# Sheet_Arduino_Mega_2560.net
KiCad netlist of a schematic drawn in Altium Designer
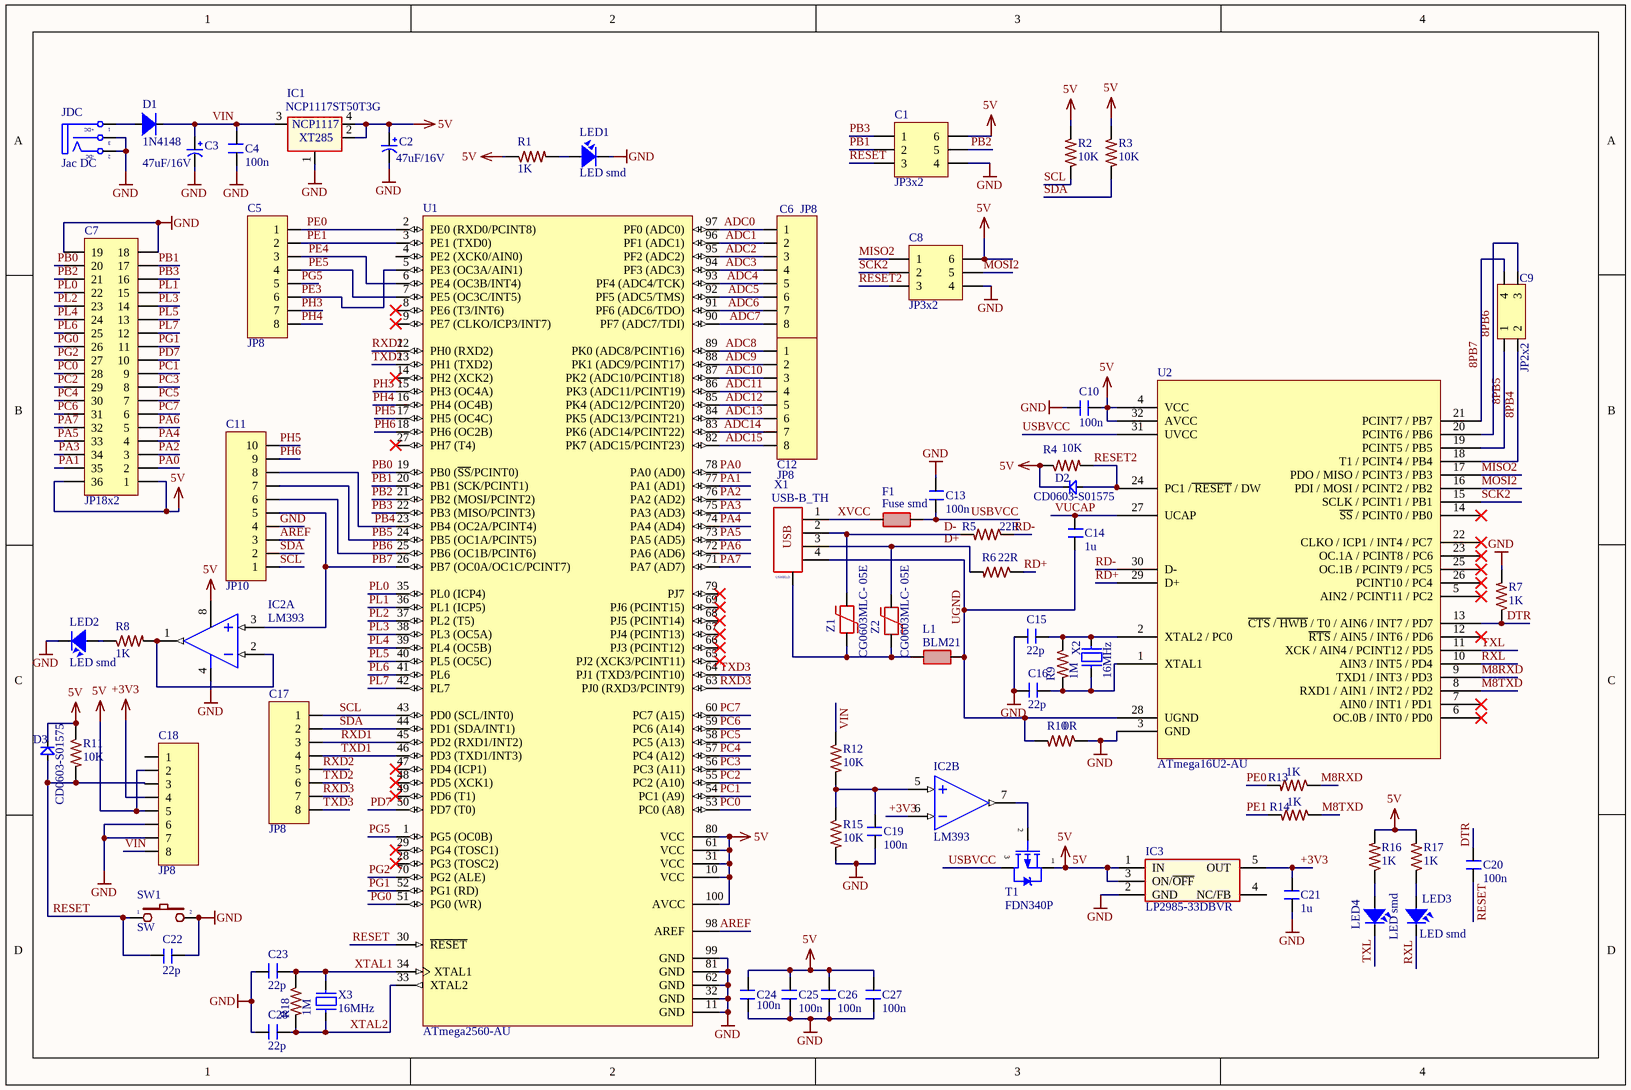
[diagram p0: Sheet_Arduino_Mega_2560.SchDoc]

(export (version "E")
  (design (tool "Eeschema 10.0.6"))
  (components
    (comp (ref "C1")
      (value "JP3x2")
      (footprint "JP3-D2T")
      (description "WR-PHD 2.54 mm Dual Socket Header")
      (fields
        (field (name "MANUFACTURER") "Würth Elektronik eiSos GmbH")
        (field (name "PARTNO") "61300621821")
        (field (name "CREATED BY") "Karrer Zheng")
      )
      (libsource (lib "APESLAB") (part "JP3x2"))
    )
    (comp (ref "C2")
      (value "47uF/16V")
      (footprint "CAP-ALU-SMD-F")
      (description "Cap 47uF/16V")
      (libsource (lib "APESLAB") (part "Cap 47uF/16V"))
    )
    (comp (ref "C3")
      (value "47uF/16V")
      (footprint "CAP-ALU-SMD-F")
      (description "Cap 47uF/16V")
      (libsource (lib "APESLAB") (part "Cap 47uF/16V"))
    )
    (comp (ref "C4")
      (value "100n")
      (footprint "cap 0603")
      (description "100nF±5%/5V")
      (libsource (lib "APESLAB") (part "Cap"))
    )
    (comp (ref "C5")
      (value "JP8")
      (footprint "JP8-C1T")
      (description "WR-PHD 2.54 mm Angled Socket Header")
      (fields
        (field (name "MANUFACTURER") "Würth Elektronik eiSos GmbH")
        (field (name "PARTNO") "613008143121")
        (field (name "CREATED BY") "Karrer Zheng")
      )
      (libsource (lib "") (part "JP8_1"))
    )
    (comp (ref "C6")
      (value "JP8")
      (footprint "JP8-C1T")
      (description "WR-PHD 2.54 mm Angled Socket Header")
      (fields
        (field (name "MANUFACTURER") "Würth Elektronik eiSos GmbH")
        (field (name "PARTNO") "613008143121")
        (field (name "CREATED BY") "Karrer Zheng")
      )
      (libsource (lib "APESLAB") (part "JP8"))
    )
    (comp (ref "C7")
      (value "JP18x2")
      (footprint "JP18-C2T")
      (description "WR-PHD 2.54 mm Dual Socket Header")
      (fields
        (field (name "MANUFACTURER") "Würth Elektronik eiSos GmbH")
        (field (name "PARTNO") "61303621821")
        (field (name "CREATED BY") "Karrer Zheng")
      )
      (libsource (lib "APESLAB") (part "JP18x2"))
    )
    (comp (ref "C8")
      (value "JP3x2")
      (footprint "JP3-D2T")
      (description "WR-PHD 2.54 mm Dual Socket Header")
      (fields
        (field (name "MANUFACTURER") "Würth Elektronik eiSos GmbH")
        (field (name "PARTNO") "61300621821")
        (field (name "CREATED BY") "Karrer Zheng")
      )
      (libsource (lib "APESLAB") (part "JP3x2"))
    )
    (comp (ref "C9")
      (value "JP2x2")
      (footprint "JP2-D2T")
      (description "WR-PHD 2.54 mm Dual Socket Header")
      (fields
        (field (name "MANUFACTURER") "Würth Elektronik eiSos GmbH")
        (field (name "PARTNO") "61300421821")
        (field (name "CREATED BY") "Karrer Zheng")
      )
      (libsource (lib "APESLAB") (part "JP2x2"))
    )
    (comp (ref "C10")
      (value "100n")
      (footprint "cap 0603")
      (description "100nF±5%/5V")
      (libsource (lib "APESLAB") (part "Cap"))
    )
    (comp (ref "C11")
      (value "JP10")
      (footprint "JP10-C1T")
      (description "WR-PHD 2.54 mm Angled Socket Header")
      (fields
        (field (name "MANUFACTURER") "Würth Elektronik eiSos GmbH")
        (field (name "PARTNO") "613010143121")
        (field (name "CREATED BY") "Karrer Zheng")
      )
      (libsource (lib "APESLAB") (part "JP10"))
    )
    (comp (ref "C12")
      (value "JP8")
      (footprint "JP8-C1T")
      (description "WR-PHD 2.54 mm Angled Socket Header")
      (fields
        (field (name "MANUFACTURER") "Würth Elektronik eiSos GmbH")
        (field (name "PARTNO") "613008143121")
        (field (name "CREATED BY") "Karrer Zheng")
      )
      (libsource (lib "APESLAB") (part "JP8"))
    )
    (comp (ref "C13")
      (value "100n")
      (footprint "cap 0603")
      (description "100nF±5%/5V")
      (libsource (lib "APESLAB") (part "Cap"))
    )
    (comp (ref "C14")
      (value "1u")
      (footprint "cap 0603")
      (description "0.47uF/1.6kV")
      (libsource (lib "APESLAB") (part "Cap"))
    )
    (comp (ref "C15")
      (value "22p")
      (footprint "cap 0603")
      (description "0.47uF/1.6kV")
      (libsource (lib "APESLAB") (part "Cap"))
    )
    (comp (ref "C16")
      (value "22p")
      (footprint "cap 0603")
      (description "0.47uF/1.6kV")
      (libsource (lib "APESLAB") (part "Cap"))
    )
    (comp (ref "C17")
      (value "JP8")
      (footprint "JP8-C1T")
      (description "WR-PHD 2.54 mm Angled Socket Header")
      (fields
        (field (name "MANUFACTURER") "Würth Elektronik eiSos GmbH")
        (field (name "PARTNO") "613008143121")
        (field (name "CREATED BY") "Karrer Zheng")
      )
      (libsource (lib "") (part "JP8_1"))
    )
    (comp (ref "C18")
      (value "JP8")
      (footprint "JP8-C1T")
      (description "WR-PHD 2.54 mm Angled Socket Header")
      (fields
        (field (name "MANUFACTURER") "Würth Elektronik eiSos GmbH")
        (field (name "PARTNO") "613008143121")
        (field (name "CREATED BY") "Karrer Zheng")
      )
      (libsource (lib "APESLAB") (part "JP8"))
    )
    (comp (ref "C19")
      (value "100n")
      (footprint "cap 0603")
      (description "100nF±5%/5V")
      (libsource (lib "APESLAB") (part "Cap"))
    )
    (comp (ref "C20")
      (value "100n")
      (footprint "cap 0603")
      (description "100nF±5%/5V")
      (libsource (lib "APESLAB") (part "Cap"))
    )
    (comp (ref "C21")
      (value "1u")
      (footprint "cap 0603")
      (description "0.47uF/1.6kV")
      (libsource (lib "APESLAB") (part "Cap"))
    )
    (comp (ref "C22")
      (value "22p")
      (footprint "cap 0603")
      (description "0.47uF/1.6kV")
      (libsource (lib "APESLAB") (part "Cap"))
    )
    (comp (ref "C23")
      (value "22p")
      (footprint "cap 0603")
      (description "0.47uF/1.6kV")
      (libsource (lib "APESLAB") (part "Cap"))
    )
    (comp (ref "C24")
      (value "100n")
      (footprint "cap 0603")
      (description "100nF±5%/5V")
      (libsource (lib "APESLAB") (part "Cap"))
    )
    (comp (ref "C25")
      (value "100n")
      (footprint "cap 0603")
      (description "100nF±5%/5V")
      (libsource (lib "APESLAB") (part "Cap"))
    )
    (comp (ref "C26")
      (value "100n")
      (footprint "cap 0603")
      (description "100nF±5%/5V")
      (libsource (lib "APESLAB") (part "Cap"))
    )
    (comp (ref "C27")
      (value "100n")
      (footprint "cap 0603")
      (description "100nF±5%/5V")
      (libsource (lib "APESLAB") (part "Cap"))
    )
    (comp (ref "C28")
      (value "22p")
      (footprint "cap 0603")
      (description "0.47uF/1.6kV")
      (libsource (lib "APESLAB") (part "Cap"))
    )
    (comp (ref "D1")
      (value "1N4148")
      (footprint "SOD80_lib")
      (libsource (lib "APESLAB") (part "Diode 1N4148"))
    )
    (comp (ref "D2")
      (value "CD0603-S01575")
      (footprint "CD0603-S01575")
      (description "diode CD0603-S01575")
      (libsource (lib "APESLAB") (part "CD0603-S01575"))
    )
    (comp (ref "D3")
      (value "CD0603-S01575")
      (footprint "CD0603-S01575")
      (description "diode CD0603-S01575")
      (libsource (lib "APESLAB") (part "CD0603-S01575"))
    )
    (comp (ref "F1") (value "Fuse smd") (footprint "Fuse_smd") (libsource (lib "APESLAB") (part "Fuse_smd")))
    (comp (ref "IC1")
      (value "NCP1117ST50T3G")
      (footprint "SOT223-4M_apes")
      (description "NCP1117")
      (libsource (lib "APESLAB") (part "NCP1117ST50T3G"))
    )
    (comp (ref "IC2")
      (value "LM393")
      (footprint "LM393")
      (description "Low-Power Dual Operational Amplifier")
      (libsource (lib "APESLAB") (part "LM393"))
    )
    (comp (ref "IC3")
      (value "LP2985-33DBVR")
      (footprint "SOT23-5")
      (libsource (lib "APESLAB") (part "LP2985"))
    )
    (comp (ref "JDC")
      (value "Jac DC")
      (footprint "DC0")
      (description "Jac DC input")
      (libsource (lib "APESLAB") (part "DCIN"))
    )
    (comp (ref "L1")
      (value "BLM21")
      (footprint "BLM21")
      (description "BLM21 EMI")
      (libsource (lib "APESLAB") (part "BLM21"))
    )
    (comp (ref "LED1")
      (value "LED smd")
      (footprint "LED-0805-Yellow")
      (libsource (lib "APESLAB") (part "LED smd"))
    )
    (comp (ref "LED2")
      (value "LED smd")
      (footprint "LED-0805-Red")
      (libsource (lib "APESLAB") (part "LED smd"))
    )
    (comp (ref "LED3")
      (value "LED smd")
      (footprint "LED-0805-Yellow")
      (libsource (lib "APESLAB") (part "LED smd"))
    )
    (comp (ref "LED4")
      (value "LED smd")
      (footprint "LED-0805-Yellow")
      (libsource (lib "APESLAB") (part "LED smd"))
    )
    (comp (ref "R1")
      (value "1K")
      (footprint "RES-SMD-0603")
      (description "res smd")
      (libsource (lib "APESLAB") (part "RES SMD"))
    )
    (comp (ref "R2")
      (value "10K")
      (footprint "RES-SMD-0603")
      (description "10K±1%/0.25W")
      (libsource (lib "APESLAB") (part "RES SMD"))
    )
    (comp (ref "R3")
      (value "10K")
      (footprint "RES-SMD-0603")
      (description "10K±1%/0.25W")
      (libsource (lib "APESLAB") (part "RES SMD"))
    )
    (comp (ref "R4")
      (value "10K")
      (footprint "RES-SMD-0603")
      (description "10K±1%/0.25W")
      (libsource (lib "APESLAB") (part "RES SMD"))
    )
    (comp (ref "R5")
      (value "22R")
      (footprint "RES-SMD-0603")
      (description "res smd")
      (libsource (lib "APESLAB") (part "RES SMD"))
    )
    (comp (ref "R6")
      (value "22R")
      (footprint "RES-SMD-0603")
      (description "res smd")
      (libsource (lib "APESLAB") (part "RES SMD"))
    )
    (comp (ref "R7")
      (value "1K")
      (footprint "RES-SMD-0603")
      (description "res smd")
      (libsource (lib "APESLAB") (part "RES SMD"))
    )
    (comp (ref "R8")
      (value "1K")
      (footprint "RES-SMD-0603")
      (description "res smd")
      (libsource (lib "APESLAB") (part "RES SMD"))
    )
    (comp (ref "R9")
      (value "1M")
      (footprint "RES-SMD-0603")
      (description "res smd")
      (libsource (lib "APESLAB") (part "RES SMD"))
    )
    (comp (ref "R10")
      (value "0R")
      (footprint "RES-SMD-0603")
      (description "res smd")
      (libsource (lib "APESLAB") (part "RES SMD"))
    )
    (comp (ref "R11")
      (value "10K")
      (footprint "RES-SMD-0603")
      (description "10K±1%/0.25W")
      (libsource (lib "APESLAB") (part "RES SMD"))
    )
    (comp (ref "R12")
      (value "10K")
      (footprint "RES-SMD-0603")
      (description "10K±1%/0.25W")
      (libsource (lib "APESLAB") (part "RES SMD"))
    )
    (comp (ref "R13")
      (value "1K")
      (footprint "RES-SMD-0603")
      (description "res smd")
      (libsource (lib "APESLAB") (part "RES SMD"))
    )
    (comp (ref "R14")
      (value "1K")
      (footprint "RES-SMD-0603")
      (description "res smd")
      (libsource (lib "APESLAB") (part "RES SMD"))
    )
    (comp (ref "R15")
      (value "10K")
      (footprint "RES-SMD-0603")
      (description "10K±1%/0.25W")
      (libsource (lib "APESLAB") (part "RES SMD"))
    )
    (comp (ref "R16")
      (value "1K")
      (footprint "RES-SMD-0603")
      (description "res smd")
      (libsource (lib "APESLAB") (part "RES SMD"))
    )
    (comp (ref "R17")
      (value "1K")
      (footprint "RES-SMD-0603")
      (description "res smd")
      (libsource (lib "APESLAB") (part "RES SMD"))
    )
    (comp (ref "R18")
      (value "1M")
      (footprint "RES-SMD-0603")
      (description "res smd")
      (libsource (lib "APESLAB") (part "RES SMD"))
    )
    (comp (ref "SW1")
      (value "SW")
      (footprint "SW-SMD_apes")
      (description "Switch button 2 pin")
      (libsource (lib "APESLAB") (part "SW2"))
    )
    (comp (ref "T1") (value "FDN340P") (footprint "SOT23-231") (libsource (lib "APESLAB") (part "FDN340D")))
    (comp (ref "U1")
      (value "ATmega2560-AU")
      (footprint "TQFP100L")
      (libsource (lib "APESLAB") (part "ATmega2560-AU"))
    )
    (comp (ref "U2")
      (value "ATmega16U2-AU")
      (footprint "TQFP32")
      (description "IC MCU 8BIT 16KB FLASH 32TQFP")
      (fields
        (field (name "MANUFACTURER") "Atmel")
        (field (name "MANUFACTURER PART NUMBER") "ATMEGA16U2-AU")
        (field (name ".CREATOR") "MM")
        (field (name ".CHECKED PCB") "RF")
        (field (name ".CHECKED SCH") "RF")
      )
      (libsource (lib "APESLAB") (part "ATmega16U2-AU"))
    )
    (comp (ref "X1") (value "USB-B_TH") (footprint "USB-C2") (libsource (lib "APESLAB") (part "USB-B")))
    (comp (ref "X2")
      (value "16MHz")
      (footprint "XT2-32.768KHz-2_V")
      (description "Crystal, 32.768 KHz, -40 to 85 degC, 3.2 x 1.5 x 0.9 mm SMD")
      (libsource (lib "APESLAB") (part "XT2_1"))
    )
    (comp (ref "X3")
      (value "16MHz")
      (footprint "XT2-32.768KHz-2_V")
      (description "Crystal, 32.768 KHz, -40 to 85 degC, 3.2 x 1.5 x 0.9 mm SMD")
      (libsource (lib "APESLAB") (part "XT2_1"))
    )
    (comp (ref "Z1")
      (value "CG0603MLC- 05E")
      (footprint "CG0603MLC- 05E")
      (description "EMI CG0603MLC- 05E")
      (libsource (lib "APESLAB") (part "CG0603MLC- 05E"))
    )
    (comp (ref "Z2")
      (value "CG0603MLC- 05E")
      (footprint "CG0603MLC- 05E")
      (description "EMI CG0603MLC- 05E")
      (libsource (lib "APESLAB") (part "CG0603MLC- 05E"))
    )
  )
  (nets
    (net (code "1") (name "+3V3") (class "Default")
      (node (ref "C18") (pin "4") (pinfunction "4_4") (pintype "passive"))
      (node (ref "C21") (pin "2") (pinfunction "2_2") (pintype "passive"))
      (node (ref "IC2") (pin "6") (pinfunction "IN-_6") (pintype "input"))
      (node (ref "IC3") (pin "5") (pinfunction "OUT_5") (pintype "passive"))
    )
    (net (code "2") (name "/8PB4") (class "Default")
      (node (ref "C9") (pin "2") (pinfunction "2_2") (pintype "passive"))
      (node (ref "U2") (pin "18") (pinfunction "T1_/_PCINT4_/_PB4_18") (pintype "passive"))
    )
    (net (code "3") (name "/8PB5") (class "Default")
      (node (ref "C9") (pin "1") (pinfunction "1_1") (pintype "passive"))
      (node (ref "U2") (pin "19") (pinfunction "PCINT5_/_PB5_19") (pintype "passive"))
    )
    (net (code "4") (name "/8PB6") (class "Default")
      (node (ref "C9") (pin "3") (pinfunction "3_3") (pintype "passive"))
      (node (ref "U2") (pin "20") (pinfunction "PCINT6_/_PB6_20") (pintype "passive"))
    )
    (net (code "5") (name "/8PB7") (class "Default")
      (node (ref "C9") (pin "4") (pinfunction "4_4") (pintype "passive"))
      (node (ref "U2") (pin "21") (pinfunction "PCINT7_/_PB7_21") (pintype "passive"))
    )
    (net (code "6") (name "/ADC0") (class "Default")
      (node (ref "C6") (pin "1") (pinfunction "1_1") (pintype "passive"))
      (node (ref "U1") (pin "97") (pinfunction "PF0_(ADC0)_97") (pintype "bidirectional"))
    )
    (net (code "7") (name "/ADC1") (class "Default")
      (node (ref "C6") (pin "2") (pinfunction "2_2") (pintype "passive"))
      (node (ref "U1") (pin "96") (pinfunction "PF1_(ADC1)_96") (pintype "bidirectional"))
    )
    (net (code "8") (name "/ADC2") (class "Default")
      (node (ref "C6") (pin "3") (pinfunction "3_3") (pintype "passive"))
      (node (ref "U1") (pin "95") (pinfunction "PF2_(ADC2)_95") (pintype "bidirectional"))
    )
    (net (code "9") (name "/ADC3") (class "Default")
      (node (ref "C6") (pin "4") (pinfunction "4_4") (pintype "passive"))
      (node (ref "U1") (pin "94") (pinfunction "PF3_(ADC3)_94") (pintype "bidirectional"))
    )
    (net (code "10") (name "/ADC4") (class "Default")
      (node (ref "C6") (pin "5") (pinfunction "5_5") (pintype "passive"))
      (node (ref "U1") (pin "93") (pinfunction "PF4_(ADC4/TCK)_93") (pintype "bidirectional"))
    )
    (net (code "11") (name "/ADC5") (class "Default")
      (node (ref "C6") (pin "6") (pinfunction "6_6") (pintype "passive"))
      (node (ref "U1") (pin "92") (pinfunction "PF5_(ADC5/TMS)_92") (pintype "bidirectional"))
    )
    (net (code "12") (name "/ADC6") (class "Default")
      (node (ref "C6") (pin "7") (pinfunction "7_7") (pintype "passive"))
      (node (ref "U1") (pin "91") (pinfunction "PF6_(ADC6/TDO)_91") (pintype "bidirectional"))
    )
    (net (code "13") (name "/ADC7") (class "Default")
      (node (ref "C6") (pin "8") (pinfunction "8_8") (pintype "passive"))
      (node (ref "U1") (pin "90") (pinfunction "PF7_(ADC7/TDI)_90") (pintype "bidirectional"))
    )
    (net (code "14") (name "/ADC8") (class "Default")
      (node (ref "C12") (pin "1") (pinfunction "1_1") (pintype "passive"))
      (node (ref "U1") (pin "89") (pinfunction "PK0_(ADC8/PCINT16)_89") (pintype "bidirectional"))
    )
    (net (code "15") (name "/ADC9") (class "Default")
      (node (ref "C12") (pin "2") (pinfunction "2_2") (pintype "passive"))
      (node (ref "U1") (pin "88") (pinfunction "PK1_(ADC9/PCINT17)_88") (pintype "bidirectional"))
    )
    (net (code "16") (name "/ADC10") (class "Default")
      (node (ref "C12") (pin "3") (pinfunction "3_3") (pintype "passive"))
      (node (ref "U1") (pin "87") (pinfunction "PK2_(ADC10/PCINT18)_87") (pintype "bidirectional"))
    )
    (net (code "17") (name "/ADC11") (class "Default")
      (node (ref "C12") (pin "4") (pinfunction "4_4") (pintype "passive"))
      (node (ref "U1") (pin "86") (pinfunction "PK3_(ADC11/PCINT19)_86") (pintype "bidirectional"))
    )
    (net (code "18") (name "/ADC12") (class "Default")
      (node (ref "C12") (pin "5") (pinfunction "5_5") (pintype "passive"))
      (node (ref "U1") (pin "85") (pinfunction "PK4_(ADC12/PCINT20)_85") (pintype "bidirectional"))
    )
    (net (code "19") (name "/ADC13") (class "Default")
      (node (ref "C12") (pin "6") (pinfunction "6_6") (pintype "passive"))
      (node (ref "U1") (pin "84") (pinfunction "PK5_(ADC13/PCINT21)_84") (pintype "bidirectional"))
    )
    (net (code "20") (name "/ADC14") (class "Default")
      (node (ref "C12") (pin "7") (pinfunction "7_7") (pintype "passive"))
      (node (ref "U1") (pin "83") (pinfunction "PK6_(ADC14/PCINT22)_83") (pintype "bidirectional"))
    )
    (net (code "21") (name "/ADC15") (class "Default")
      (node (ref "C12") (pin "8") (pinfunction "8_8") (pintype "passive"))
      (node (ref "U1") (pin "82") (pinfunction "PK7_(ADC15/PCINT23)_82") (pintype "bidirectional"))
    )
    (net (code "22") (name "/AREF") (class "Default")
      (node (ref "C11") (pin "3") (pinfunction "3_3") (pintype "passive"))
      (node (ref "U1") (pin "98") (pinfunction "AREF_98") (pintype "power_in"))
    )
    (net (code "23") (name "/D+") (class "Default")
      (node (ref "R6") (pin "2") (pinfunction "2_2") (pintype "passive"))
      (node (ref "X1") (pin "3") (pinfunction "3_3") (pintype "passive"))
      (node (ref "Z2") (pin "2") (pinfunction "2_2") (pintype "passive"))
    )
    (net (code "24") (name "/D-") (class "Default")
      (node (ref "R5") (pin "2") (pinfunction "2_2") (pintype "passive"))
      (node (ref "X1") (pin "2") (pinfunction "2_2") (pintype "passive"))
      (node (ref "Z1") (pin "2") (pinfunction "2_2") (pintype "passive"))
    )
    (net (code "25") (name "/DTR") (class "Default")
      (node (ref "C20") (pin "1") (pinfunction "1_1") (pintype "passive"))
      (node (ref "R7") (pin "1") (pinfunction "1_1") (pintype "passive"))
      (node (ref "U2") (pin "13") (pinfunction "~{CTS}_/~{_HWB}_/_T0_/_AIN6_/_INT7_/_PD7_13") (pintype "passive"))
    )
    (net (code "26") (name "/M8RXD") (class "Default")
      (node (ref "R13") (pin "1") (pinfunction "1_1") (pintype "passive"))
      (node (ref "U2") (pin "9") (pinfunction "TXD1_/_INT3_/_PD3_9") (pintype "passive"))
    )
    (net (code "27") (name "/M8TXD") (class "Default")
      (node (ref "R14") (pin "1") (pinfunction "1_1") (pintype "passive"))
      (node (ref "U2") (pin "8") (pinfunction "RXD1_/_AIN1_/_INT2_/_PD2_8") (pintype "passive"))
    )
    (net (code "28") (name "/MISO2") (class "Default")
      (node (ref "C8") (pin "1") (pinfunction "1_1") (pintype "passive"))
      (node (ref "U2") (pin "17") (pinfunction "PDO_/_MISO_/_PCINT3_/_PB3_17") (pintype "passive"))
    )
    (net (code "29") (name "/MOSI2") (class "Default")
      (node (ref "C8") (pin "5") (pinfunction "5_5") (pintype "passive"))
      (node (ref "U2") (pin "16") (pinfunction "PDI_/_MOSI_/_PCINT2_/_PB2_16") (pintype "passive"))
    )
    (net (code "30") (name "/PA0") (class "Default")
      (node (ref "C7") (pin "2") (pinfunction "2_2") (pintype "passive"))
      (node (ref "U1") (pin "78") (pinfunction "PA0_(AD0)_78") (pintype "bidirectional"))
    )
    (net (code "31") (name "/PA1") (class "Default")
      (node (ref "C7") (pin "35") (pinfunction "35_35") (pintype "passive"))
      (node (ref "U1") (pin "77") (pinfunction "PA1_(AD1)_77") (pintype "bidirectional"))
    )
    (net (code "32") (name "/PA2") (class "Default")
      (node (ref "C7") (pin "3") (pinfunction "3_3") (pintype "passive"))
      (node (ref "U1") (pin "76") (pinfunction "PA2_(AD2)_76") (pintype "bidirectional"))
    )
    (net (code "33") (name "/PA3") (class "Default")
      (node (ref "C7") (pin "34") (pinfunction "34_34") (pintype "passive"))
      (node (ref "U1") (pin "75") (pinfunction "PA3_(AD3)_75") (pintype "bidirectional"))
    )
    (net (code "34") (name "/PA4") (class "Default")
      (node (ref "C7") (pin "4") (pinfunction "4_4") (pintype "passive"))
      (node (ref "U1") (pin "74") (pinfunction "PA4_(AD4)_74") (pintype "bidirectional"))
    )
    (net (code "35") (name "/PA5") (class "Default")
      (node (ref "C7") (pin "33") (pinfunction "33_33") (pintype "passive"))
      (node (ref "U1") (pin "73") (pinfunction "PA5_(AD5)_73") (pintype "bidirectional"))
    )
    (net (code "36") (name "/PA6") (class "Default")
      (node (ref "C7") (pin "5") (pinfunction "5_5") (pintype "passive"))
      (node (ref "U1") (pin "72") (pinfunction "PA6_(AD6)_72") (pintype "bidirectional"))
    )
    (net (code "37") (name "/PA7") (class "Default")
      (node (ref "C7") (pin "32") (pinfunction "32_32") (pintype "passive"))
      (node (ref "U1") (pin "71") (pinfunction "PA7_(AD7)_71") (pintype "bidirectional"))
    )
    (net (code "38") (name "/PB0") (class "Default")
      (node (ref "C7") (pin "20") (pinfunction "20_20") (pintype "passive"))
      (node (ref "U1") (pin "19") (pinfunction "PB0_(~{SS}/PCINT0)_19") (pintype "bidirectional"))
    )
    (net (code "39") (name "/PB1") (class "Default")
      (node (ref "C1") (pin "2") (pinfunction "2_2") (pintype "passive"))
      (node (ref "C7") (pin "17") (pinfunction "17_17") (pintype "passive"))
      (node (ref "U1") (pin "20") (pinfunction "PB1_(SCK/PCINT1)_20") (pintype "bidirectional"))
    )
    (net (code "40") (name "/PB2") (class "Default")
      (node (ref "C1") (pin "5") (pinfunction "5_5") (pintype "passive"))
      (node (ref "C7") (pin "21") (pinfunction "21_21") (pintype "passive"))
      (node (ref "U1") (pin "21") (pinfunction "PB2_(MOSI/PCINT2)_21") (pintype "bidirectional"))
    )
    (net (code "41") (name "/PB3") (class "Default")
      (node (ref "C1") (pin "1") (pinfunction "1_1") (pintype "passive"))
      (node (ref "C7") (pin "16") (pinfunction "16_16") (pintype "passive"))
      (node (ref "U1") (pin "22") (pinfunction "PB3_(MISO/PCINT3)_22") (pintype "bidirectional"))
    )
    (net (code "42") (name "/PB4") (class "Default")
      (node (ref "C11") (pin "8") (pinfunction "8_8") (pintype "passive"))
      (node (ref "U1") (pin "23") (pinfunction "PB4_(OC2A/PCINT4)_23") (pintype "bidirectional"))
    )
    (net (code "43") (name "/PB5") (class "Default")
      (node (ref "C11") (pin "7") (pinfunction "7_7") (pintype "passive"))
      (node (ref "U1") (pin "24") (pinfunction "PB5_(OC1A/PCINT5)_24") (pintype "bidirectional"))
    )
    (net (code "44") (name "/PB6") (class "Default")
      (node (ref "C11") (pin "6") (pinfunction "6_6") (pintype "passive"))
      (node (ref "U1") (pin "25") (pinfunction "PB6_(OC1B/PCINT6)_25") (pintype "bidirectional"))
    )
    (net (code "45") (name "/PB7") (class "Default")
      (node (ref "C11") (pin "5") (pinfunction "5_5") (pintype "passive"))
      (node (ref "IC2") (pin "3") (pinfunction "IN+_3") (pintype "input"))
      (node (ref "U1") (pin "26") (pinfunction "PB7_(OC0A/OC1C/PCINT7)_26") (pintype "bidirectional"))
    )
    (net (code "46") (name "/PC0") (class "Default")
      (node (ref "C7") (pin "28") (pinfunction "28_28") (pintype "passive"))
      (node (ref "U1") (pin "53") (pinfunction "PC0_(A8)_53") (pintype "bidirectional"))
    )
    (net (code "47") (name "/PC1") (class "Default")
      (node (ref "C7") (pin "9") (pinfunction "9_9") (pintype "passive"))
      (node (ref "U1") (pin "54") (pinfunction "PC1_(A9)_54") (pintype "bidirectional"))
    )
    (net (code "48") (name "/PC2") (class "Default")
      (node (ref "C7") (pin "29") (pinfunction "29_29") (pintype "passive"))
      (node (ref "U1") (pin "55") (pinfunction "PC2_(A10)_55") (pintype "bidirectional"))
    )
    (net (code "49") (name "/PC3") (class "Default")
      (node (ref "C7") (pin "8") (pinfunction "8_8") (pintype "passive"))
      (node (ref "U1") (pin "56") (pinfunction "PC3_(A11)_56") (pintype "bidirectional"))
    )
    (net (code "50") (name "/PC4") (class "Default")
      (node (ref "C7") (pin "30") (pinfunction "30_30") (pintype "passive"))
      (node (ref "U1") (pin "57") (pinfunction "PC4_(A12)_57") (pintype "bidirectional"))
    )
    (net (code "51") (name "/PC5") (class "Default")
      (node (ref "C7") (pin "7") (pinfunction "7_7") (pintype "passive"))
      (node (ref "U1") (pin "58") (pinfunction "PC5_(A13)_58") (pintype "bidirectional"))
    )
    (net (code "52") (name "/PC6") (class "Default")
      (node (ref "C7") (pin "31") (pinfunction "31_31") (pintype "passive"))
      (node (ref "U1") (pin "59") (pinfunction "PC6_(A14)_59") (pintype "bidirectional"))
    )
    (net (code "53") (name "/PC7") (class "Default")
      (node (ref "C7") (pin "6") (pinfunction "6_6") (pintype "passive"))
      (node (ref "U1") (pin "60") (pinfunction "PC7_(A15)_60") (pintype "bidirectional"))
    )
    (net (code "54") (name "/PD7") (class "Default")
      (node (ref "C7") (pin "10") (pinfunction "10_10") (pintype "passive"))
      (node (ref "U1") (pin "50") (pinfunction "PD7_(T0)_50") (pintype "bidirectional"))
    )
    (net (code "55") (name "/PE0") (class "Default")
      (node (ref "C5") (pin "1") (pinfunction "1_1") (pintype "passive"))
      (node (ref "R13") (pin "2") (pinfunction "2_2") (pintype "passive"))
      (node (ref "U1") (pin "2") (pinfunction "PE0_(RXD0/PCINT8)_2") (pintype "bidirectional"))
    )
    (net (code "56") (name "/PE1") (class "Default")
      (node (ref "C5") (pin "2") (pinfunction "2_2") (pintype "passive"))
      (node (ref "R14") (pin "2") (pinfunction "2_2") (pintype "passive"))
      (node (ref "U1") (pin "3") (pinfunction "PE1_(TXD0)_3") (pintype "bidirectional"))
    )
    (net (code "57") (name "/PE3") (class "Default")
      (node (ref "C5") (pin "6") (pinfunction "6_6") (pintype "passive"))
      (node (ref "U1") (pin "5") (pinfunction "PE3_(OC3A/AIN1)_5") (pintype "bidirectional"))
    )
    (net (code "58") (name "/PE4") (class "Default")
      (node (ref "C5") (pin "3") (pinfunction "3_3") (pintype "passive"))
      (node (ref "U1") (pin "6") (pinfunction "PE4_(OC3B/INT4)_6") (pintype "bidirectional"))
    )
    (net (code "59") (name "/PE5") (class "Default")
      (node (ref "C5") (pin "4") (pinfunction "4_4") (pintype "passive"))
      (node (ref "U1") (pin "7") (pinfunction "PE5_(OC3C/INT5)_7") (pintype "bidirectional"))
    )
    (net (code "60") (name "/PG0") (class "Default")
      (node (ref "C7") (pin "26") (pinfunction "26_26") (pintype "passive"))
      (node (ref "U1") (pin "51") (pinfunction "PG0_(WR)_51") (pintype "bidirectional"))
    )
    (net (code "61") (name "/PG1") (class "Default")
      (node (ref "C7") (pin "11") (pinfunction "11_11") (pintype "passive"))
      (node (ref "U1") (pin "52") (pinfunction "PG1_(RD)_52") (pintype "bidirectional"))
    )
    (net (code "62") (name "/PG2") (class "Default")
      (node (ref "C7") (pin "27") (pinfunction "27_27") (pintype "passive"))
      (node (ref "U1") (pin "70") (pinfunction "PG2_(ALE)_70") (pintype "bidirectional"))
    )
    (net (code "63") (name "/PG5") (class "Default")
      (node (ref "C5") (pin "5") (pinfunction "5_5") (pintype "passive"))
      (node (ref "U1") (pin "1") (pinfunction "PG5_(OC0B)_1") (pintype "bidirectional"))
    )
    (net (code "64") (name "/PH3") (class "Default")
      (node (ref "C5") (pin "7") (pinfunction "7_7") (pintype "passive"))
      (node (ref "U1") (pin "15") (pinfunction "PH3_(OC4A)_15") (pintype "bidirectional"))
    )
    (net (code "65") (name "/PH4") (class "Default")
      (node (ref "C5") (pin "8") (pinfunction "8_8") (pintype "passive"))
      (node (ref "U1") (pin "16") (pinfunction "PH4_(OC4B)_16") (pintype "bidirectional"))
    )
    (net (code "66") (name "/PH5") (class "Default")
      (node (ref "C11") (pin "10") (pinfunction "10_10") (pintype "passive"))
      (node (ref "U1") (pin "17") (pinfunction "PH5_(OC4C)_17") (pintype "bidirectional"))
    )
    (net (code "67") (name "/PH6") (class "Default")
      (node (ref "C11") (pin "9") (pinfunction "9_9") (pintype "passive"))
      (node (ref "U1") (pin "18") (pinfunction "PH6_(OC2B)_18") (pintype "bidirectional"))
    )
    (net (code "68") (name "/PL0") (class "Default")
      (node (ref "C7") (pin "22") (pinfunction "22_22") (pintype "passive"))
      (node (ref "U1") (pin "35") (pinfunction "PL0_(ICP4)_35") (pintype "bidirectional"))
    )
    (net (code "69") (name "/PL1") (class "Default")
      (node (ref "C7") (pin "15") (pinfunction "15_15") (pintype "passive"))
      (node (ref "U1") (pin "36") (pinfunction "PL1_(ICP5)_36") (pintype "bidirectional"))
    )
    (net (code "70") (name "/PL2") (class "Default")
      (node (ref "C7") (pin "23") (pinfunction "23_23") (pintype "passive"))
      (node (ref "U1") (pin "37") (pinfunction "PL2_(T5)_37") (pintype "bidirectional"))
    )
    (net (code "71") (name "/PL3") (class "Default")
      (node (ref "C7") (pin "14") (pinfunction "14_14") (pintype "passive"))
      (node (ref "U1") (pin "38") (pinfunction "PL3_(OC5A)_38") (pintype "bidirectional"))
    )
    (net (code "72") (name "/PL4") (class "Default")
      (node (ref "C7") (pin "24") (pinfunction "24_24") (pintype "passive"))
      (node (ref "U1") (pin "39") (pinfunction "PL4_(OC5B)_39") (pintype "bidirectional"))
    )
    (net (code "73") (name "/PL5") (class "Default")
      (node (ref "C7") (pin "13") (pinfunction "13_13") (pintype "passive"))
      (node (ref "U1") (pin "40") (pinfunction "PL5_(OC5C)_40") (pintype "bidirectional"))
    )
    (net (code "74") (name "/PL6") (class "Default")
      (node (ref "C7") (pin "25") (pinfunction "25_25") (pintype "passive"))
      (node (ref "U1") (pin "41") (pinfunction "PL6_41") (pintype "bidirectional"))
    )
    (net (code "75") (name "/PL7") (class "Default")
      (node (ref "C7") (pin "12") (pinfunction "12_12") (pintype "passive"))
      (node (ref "U1") (pin "42") (pinfunction "PL7_42") (pintype "bidirectional"))
    )
    (net (code "76") (name "/RD+") (class "Default")
      (node (ref "R6") (pin "1") (pinfunction "1_1") (pintype "passive"))
      (node (ref "U2") (pin "29") (pinfunction "D+_29") (pintype "passive"))
    )
    (net (code "77") (name "/RD-") (class "Default")
      (node (ref "R5") (pin "1") (pinfunction "1_1") (pintype "passive"))
      (node (ref "U2") (pin "30") (pinfunction "D-_30") (pintype "passive"))
    )
    (net (code "78") (name "/RESET") (class "Default")
      (node (ref "C1") (pin "3") (pinfunction "3_3") (pintype "passive"))
      (node (ref "C18") (pin "3") (pinfunction "3_3") (pintype "passive"))
      (node (ref "C20") (pin "2") (pinfunction "2_2") (pintype "passive"))
      (node (ref "C22") (pin "2") (pinfunction "2_2") (pintype "passive"))
      (node (ref "D3") (pin "1") (pinfunction "A_1") (pintype "passive"))
      (node (ref "R11") (pin "2") (pinfunction "2_2") (pintype "passive"))
      (node (ref "SW1") (pin "1") (pinfunction "1_1") (pintype "passive"))
      (node (ref "U1") (pin "30") (pinfunction "~{RESET}_30") (pintype "input"))
    )
    (net (code "79") (name "/RESET2") (class "Default")
      (node (ref "C8") (pin "3") (pinfunction "3_3") (pintype "passive"))
      (node (ref "D2") (pin "1") (pinfunction "A_1") (pintype "passive"))
      (node (ref "R4") (pin "2") (pinfunction "2_2") (pintype "passive"))
      (node (ref "U2") (pin "24") (pinfunction "PC1_/~{_RESET}_/_DW_24") (pintype "passive"))
    )
    (net (code "80") (name "/RXD1") (class "Default")
      (node (ref "C17") (pin "3") (pinfunction "3_3") (pintype "passive"))
      (node (ref "U1") (pin "45") (pinfunction "PD2_(RXD1/INT2)_45") (pintype "bidirectional"))
    )
    (net (code "81") (name "/RXD2") (class "Default")
      (node (ref "C17") (pin "5") (pinfunction "5_5") (pintype "passive"))
      (node (ref "U1") (pin "12") (pinfunction "PH0_(RXD2)_12") (pintype "bidirectional"))
    )
    (net (code "82") (name "/RXD3") (class "Default")
      (node (ref "C17") (pin "7") (pinfunction "7_7") (pintype "passive"))
      (node (ref "U1") (pin "63") (pinfunction "PJ0_(RXD3/PCINT9)_63") (pintype "bidirectional"))
    )
    (net (code "83") (name "/RXL") (class "Default")
      (node (ref "LED3") (pin "2") (pinfunction "2_2") (pintype "passive"))
      (node (ref "U2") (pin "10") (pinfunction "AIN3_/_INT5_/_PD4_10") (pintype "passive"))
    )
    (net (code "84") (name "/SCK2") (class "Default")
      (node (ref "C8") (pin "2") (pinfunction "2_2") (pintype "passive"))
      (node (ref "U2") (pin "15") (pinfunction "SCLK_/_PCINT1_/_PB1_15") (pintype "passive"))
    )
    (net (code "85") (name "/SCL") (class "Default")
      (node (ref "C11") (pin "1") (pinfunction "1_1") (pintype "passive"))
      (node (ref "C17") (pin "1") (pinfunction "1_1") (pintype "passive"))
      (node (ref "R2") (pin "2") (pinfunction "2_2") (pintype "passive"))
      (node (ref "U1") (pin "43") (pinfunction "PD0_(SCL/INT0)_43") (pintype "bidirectional"))
    )
    (net (code "86") (name "/SDA") (class "Default")
      (node (ref "C11") (pin "2") (pinfunction "2_2") (pintype "passive"))
      (node (ref "C17") (pin "2") (pinfunction "2_2") (pintype "passive"))
      (node (ref "R3") (pin "2") (pinfunction "2_2") (pintype "passive"))
      (node (ref "U1") (pin "44") (pinfunction "PD1_(SDA/INT1)_44") (pintype "bidirectional"))
    )
    (net (code "87") (name "/TXD1") (class "Default")
      (node (ref "C17") (pin "4") (pinfunction "4_4") (pintype "passive"))
      (node (ref "U1") (pin "46") (pinfunction "PD3_(TXD1/INT3)_46") (pintype "bidirectional"))
    )
    (net (code "88") (name "/TXD2") (class "Default")
      (node (ref "C17") (pin "6") (pinfunction "6_6") (pintype "passive"))
      (node (ref "U1") (pin "13") (pinfunction "PH1_(TXD2)_13") (pintype "bidirectional"))
    )
    (net (code "89") (name "/TXD3") (class "Default")
      (node (ref "C17") (pin "8") (pinfunction "8_8") (pintype "passive"))
      (node (ref "U1") (pin "64") (pinfunction "PJ1_(TXD3/PCINT10)_64") (pintype "bidirectional"))
    )
    (net (code "90") (name "/TXL") (class "Default")
      (node (ref "LED4") (pin "2") (pinfunction "2_2") (pintype "passive"))
      (node (ref "U2") (pin "11") (pinfunction "XCK_/_AIN4_/_PCINT12_/_PD5_11") (pintype "passive"))
    )
    (net (code "91") (name "/UGND") (class "Default")
      (node (ref "C14") (pin "2") (pinfunction "2_2") (pintype "passive"))
      (node (ref "L1") (pin "2") (pinfunction "2_2") (pintype "passive"))
      (node (ref "R10") (pin "2") (pinfunction "2_2") (pintype "passive"))
      (node (ref "U2") (pin "28") (pinfunction "UGND_28") (pintype "passive"))
      (node (ref "X1") (pin "4") (pinfunction "4_4") (pintype "passive"))
    )
    (net (code "92") (name "/USBVCC") (class "Default")
      (node (ref "C13") (pin "2") (pinfunction "2_2") (pintype "passive"))
      (node (ref "F1") (pin "2") (pinfunction "2_2") (pintype "passive"))
      (node (ref "T1") (pin "3") (pinfunction "D_3") (pintype "passive"))
      (node (ref "U2") (pin "31") (pinfunction "UVCC_31") (pintype "passive"))
    )
    (net (code "93") (name "/VIN") (class "Default")
      (node (ref "C18") (pin "8") (pinfunction "8_8") (pintype "passive"))
      (node (ref "C3") (pin "1") (pinfunction "1_1") (pintype "passive"))
      (node (ref "C4") (pin "2") (pinfunction "2_2") (pintype "passive"))
      (node (ref "D1") (pin "K") (pinfunction "K_K") (pintype "passive"))
      (node (ref "IC1") (pin "3") (pinfunction "3_3") (pintype "passive"))
      (node (ref "R12") (pin "1") (pinfunction "1_1") (pintype "passive"))
    )
    (net (code "94") (name "/VUCAP") (class "Default")
      (node (ref "C14") (pin "1") (pinfunction "1_1") (pintype "passive"))
      (node (ref "U2") (pin "27") (pinfunction "UCAP_27") (pintype "passive"))
    )
    (net (code "95") (name "/XTAL1") (class "Default")
      (node (ref "C23") (pin "2") (pinfunction "2_2") (pintype "passive"))
      (node (ref "R18") (pin "1") (pinfunction "1_1") (pintype "passive"))
      (node (ref "U1") (pin "34") (pinfunction "XTAL1_34") (pintype "input"))
      (node (ref "X3") (pin "2") (pinfunction "2_2") (pintype "passive"))
    )
    (net (code "96") (name "/XTAL2") (class "Default")
      (node (ref "C28") (pin "2") (pinfunction "2_2") (pintype "passive"))
      (node (ref "R18") (pin "2") (pinfunction "2_2") (pintype "passive"))
      (node (ref "U1") (pin "33") (pinfunction "XTAL2_33") (pintype "output"))
      (node (ref "X3") (pin "1") (pinfunction "1_1") (pintype "passive"))
    )
    (net (code "97") (name "/XVCC") (class "Default")
      (node (ref "F1") (pin "1") (pinfunction "1_1") (pintype "passive"))
      (node (ref "X1") (pin "1") (pinfunction "1_1") (pintype "passive"))
    )
    (net (code "98") (name "5V") (class "Default")
      (node (ref "C1") (pin "6") (pinfunction "6_6") (pintype "passive"))
      (node (ref "C10") (pin "1") (pinfunction "1_1") (pintype "passive"))
      (node (ref "C18") (pin "2") (pinfunction "2_2") (pintype "passive"))
      (node (ref "C18") (pin "5") (pinfunction "5_5") (pintype "passive"))
      (node (ref "C2") (pin "1") (pinfunction "1_1") (pintype "passive"))
      (node (ref "C24") (pin "2") (pinfunction "2_2") (pintype "passive"))
      (node (ref "C25") (pin "2") (pinfunction "2_2") (pintype "passive"))
      (node (ref "C26") (pin "2") (pinfunction "2_2") (pintype "passive"))
      (node (ref "C27") (pin "2") (pinfunction "2_2") (pintype "passive"))
      (node (ref "C7") (pin "1") (pinfunction "1_1") (pintype "passive"))
      (node (ref "C7") (pin "36") (pinfunction "36_36") (pintype "passive"))
      (node (ref "C8") (pin "6") (pinfunction "6_6") (pintype "passive"))
      (node (ref "D2") (pin "2") (pinfunction "K_2") (pintype "passive"))
      (node (ref "D3") (pin "2") (pinfunction "K_2") (pintype "passive"))
      (node (ref "IC1") (pin "2") (pinfunction "2_2") (pintype "passive"))
      (node (ref "IC1") (pin "4") (pinfunction "4_4") (pintype "passive"))
      (node (ref "IC2") (pin "8") (pinfunction "+V_8") (pintype "passive"))
      (node (ref "IC3") (pin "1") (pinfunction "IN_1") (pintype "passive"))
      (node (ref "IC3") (pin "3") (pinfunction "ON/~{OFF}_3") (pintype "passive"))
      (node (ref "R1") (pin "1") (pinfunction "1_1") (pintype "passive"))
      (node (ref "R11") (pin "1") (pinfunction "1_1") (pintype "passive"))
      (node (ref "R16") (pin "2") (pinfunction "2_2") (pintype "passive"))
      (node (ref "R17") (pin "2") (pinfunction "2_2") (pintype "passive"))
      (node (ref "R2") (pin "1") (pinfunction "1_1") (pintype "passive"))
      (node (ref "R3") (pin "1") (pinfunction "1_1") (pintype "passive"))
      (node (ref "R4") (pin "1") (pinfunction "1_1") (pintype "passive"))
      (node (ref "T1") (pin "1") (pinfunction "S_1") (pintype "passive"))
      (node (ref "U1") (pin "10") (pinfunction "VCC_10") (pintype "power_in"))
      (node (ref "U1") (pin "100") (pinfunction "AVCC_100") (pintype "power_in"))
      (node (ref "U1") (pin "31") (pinfunction "VCC_31") (pintype "power_in"))
      (node (ref "U1") (pin "61") (pinfunction "VCC_61") (pintype "power_in"))
      (node (ref "U1") (pin "80") (pinfunction "VCC_80") (pintype "power_in"))
      (node (ref "U2") (pin "32") (pinfunction "AVCC_32") (pintype "passive"))
      (node (ref "U2") (pin "4") (pinfunction "VCC_4") (pintype "passive"))
    )
    (net (code "99") (name "GND") (class "Default")
      (node (ref "C1") (pin "4") (pinfunction "4_4") (pintype "passive"))
      (node (ref "C10") (pin "2") (pinfunction "2_2") (pintype "passive"))
      (node (ref "C11") (pin "4") (pinfunction "4_4") (pintype "passive"))
      (node (ref "C13") (pin "1") (pinfunction "1_1") (pintype "passive"))
      (node (ref "C15") (pin "1") (pinfunction "1_1") (pintype "passive"))
      (node (ref "C16") (pin "1") (pinfunction "1_1") (pintype "passive"))
      (node (ref "C18") (pin "6") (pinfunction "6_6") (pintype "passive"))
      (node (ref "C18") (pin "7") (pinfunction "7_7") (pintype "passive"))
      (node (ref "C19") (pin "1") (pinfunction "1_1") (pintype "passive"))
      (node (ref "C2") (pin "2") (pinfunction "2_2") (pintype "passive"))
      (node (ref "C21") (pin "1") (pinfunction "1_1") (pintype "passive"))
      (node (ref "C22") (pin "1") (pinfunction "1_1") (pintype "passive"))
      (node (ref "C23") (pin "1") (pinfunction "1_1") (pintype "passive"))
      (node (ref "C24") (pin "1") (pinfunction "1_1") (pintype "passive"))
      (node (ref "C25") (pin "1") (pinfunction "1_1") (pintype "passive"))
      (node (ref "C26") (pin "1") (pinfunction "1_1") (pintype "passive"))
      (node (ref "C27") (pin "1") (pinfunction "1_1") (pintype "passive"))
      (node (ref "C28") (pin "1") (pinfunction "1_1") (pintype "passive"))
      (node (ref "C3") (pin "2") (pinfunction "2_2") (pintype "passive"))
      (node (ref "C4") (pin "1") (pinfunction "1_1") (pintype "passive"))
      (node (ref "C7") (pin "18") (pinfunction "18_18") (pintype "passive"))
      (node (ref "C7") (pin "19") (pinfunction "19_19") (pintype "passive"))
      (node (ref "C8") (pin "4") (pinfunction "4_4") (pintype "passive"))
      (node (ref "IC1") (pin "1") (pinfunction "1_1") (pintype "passive"))
      (node (ref "IC2") (pin "4") (pinfunction "-V_4") (pintype "passive"))
      (node (ref "IC3") (pin "2") (pinfunction "GND_2") (pintype "passive"))
      (node (ref "JDC") (pin "2") (pinfunction "TN_2") (pintype "passive"))
      (node (ref "JDC") (pin "3") (pinfunction "S_3") (pintype "power_in"))
      (node (ref "LED1") (pin "2") (pinfunction "2_2") (pintype "passive"))
      (node (ref "LED2") (pin "2") (pinfunction "2_2") (pintype "passive"))
      (node (ref "R10") (pin "1") (pinfunction "1_1") (pintype "passive"))
      (node (ref "R15") (pin "2") (pinfunction "2_2") (pintype "passive"))
      (node (ref "R7") (pin "2") (pinfunction "2_2") (pintype "passive"))
      (node (ref "SW1") (pin "2") (pinfunction "2_2") (pintype "passive"))
      (node (ref "U1") (pin "11") (pinfunction "GND_11") (pintype "power_in"))
      (node (ref "U1") (pin "32") (pinfunction "GND_32") (pintype "power_in"))
      (node (ref "U1") (pin "62") (pinfunction "GND_62") (pintype "power_in"))
      (node (ref "U1") (pin "81") (pinfunction "GND_81") (pintype "power_in"))
      (node (ref "U1") (pin "99") (pinfunction "GND_99") (pintype "power_in"))
      (node (ref "U2") (pin "3") (pinfunction "GND_3") (pintype "passive"))
    )
    (net (code "100") (name "Net-(IC2A-IN-)") (class "Default")
      (node (ref "IC2") (pin "1") (pinfunction "OUT_1") (pintype "output"))
      (node (ref "IC2") (pin "2") (pinfunction "IN-_2") (pintype "input"))
      (node (ref "R8") (pin "2") (pinfunction "2_2") (pintype "passive"))
    )
    (net (code "101") (name "Net-(IC2B-IN+)") (class "Default")
      (node (ref "C19") (pin "2") (pinfunction "2_2") (pintype "passive"))
      (node (ref "IC2") (pin "5") (pinfunction "IN+_5") (pintype "input"))
      (node (ref "R12") (pin "2") (pinfunction "2_2") (pintype "passive"))
      (node (ref "R15") (pin "1") (pinfunction "1_1") (pintype "passive"))
    )
    (net (code "102") (name "Net-(IC2B-OUT)") (class "Default")
      (node (ref "IC2") (pin "7") (pinfunction "OUT_7") (pintype "output"))
      (node (ref "T1") (pin "2") (pinfunction "G_2") (pintype "passive"))
    )
    (net (code "103") (name "Net-(JDC-T)") (class "Default")
      (node (ref "D1") (pin "A") (pinfunction "A_A") (pintype "passive"))
      (node (ref "JDC") (pin "1") (pinfunction "T_1") (pintype "passive"))
    )
    (net (code "104") (name "Net-(L1-Pad1)") (class "Default")
      (node (ref "L1") (pin "1") (pinfunction "1_1") (pintype "passive"))
      (node (ref "X1") (pin "5") (pinfunction "5_5") (pintype "passive"))
      (node (ref "Z1") (pin "1") (pinfunction "1_1") (pintype "passive"))
      (node (ref "Z2") (pin "1") (pinfunction "1_1") (pintype "passive"))
    )
    (net (code "105") (name "Net-(LED1-Pad1)") (class "Default")
      (node (ref "LED1") (pin "1") (pinfunction "1_1") (pintype "passive"))
      (node (ref "R1") (pin "2") (pinfunction "2_2") (pintype "passive"))
    )
    (net (code "106") (name "Net-(LED2-Pad1)") (class "Default")
      (node (ref "LED2") (pin "1") (pinfunction "1_1") (pintype "passive"))
      (node (ref "R8") (pin "1") (pinfunction "1_1") (pintype "passive"))
    )
    (net (code "107") (name "Net-(LED3-Pad1)") (class "Default")
      (node (ref "LED3") (pin "1") (pinfunction "1_1") (pintype "passive"))
      (node (ref "R17") (pin "1") (pinfunction "1_1") (pintype "passive"))
    )
    (net (code "108") (name "Net-(LED4-Pad1)") (class "Default")
      (node (ref "LED4") (pin "1") (pinfunction "1_1") (pintype "passive"))
      (node (ref "R16") (pin "1") (pinfunction "1_1") (pintype "passive"))
    )
    (net (code "109") (name "Net-(U2-XTAL1)") (class "Default")
      (node (ref "C16") (pin "2") (pinfunction "2_2") (pintype "passive"))
      (node (ref "R9") (pin "2") (pinfunction "2_2") (pintype "passive"))
      (node (ref "U2") (pin "1") (pinfunction "XTAL1_1") (pintype "passive"))
      (node (ref "X2") (pin "1") (pinfunction "1_1") (pintype "passive"))
    )
    (net (code "110") (name "Net-(U2-XTAL2_{slash}_PC0)") (class "Default")
      (node (ref "C15") (pin "2") (pinfunction "2_2") (pintype "passive"))
      (node (ref "R9") (pin "1") (pinfunction "1_1") (pintype "passive"))
      (node (ref "U2") (pin "2") (pinfunction "XTAL2_/_PC0_2") (pintype "passive"))
      (node (ref "X2") (pin "2") (pinfunction "2_2") (pintype "passive"))
    )
    (net (code "111") (name "unconnected-(C18-Pad1)") (class "Default")
      (node (ref "C18") (pin "1") (pinfunction "1_1") (pintype "passive"))
    )
    (net (code "112") (name "unconnected-(IC3-NC{slash}FB-Pad4)") (class "Default")
      (node (ref "IC3") (pin "4") (pinfunction "NC/FB_4") (pintype "passive"))
    )
    (net (code "113") (name "unconnected-(U1-PD4_(ICP1)-Pad47)") (class "Default")
      (node (ref "U1") (pin "47") (pinfunction "PD4_(ICP1)_47") (pintype "bidirectional+no_connect"))
    )
    (net (code "114") (name "unconnected-(U1-PD5_(XCK1)-Pad48)") (class "Default")
      (node (ref "U1") (pin "48") (pinfunction "PD5_(XCK1)_48") (pintype "bidirectional+no_connect"))
    )
    (net (code "115") (name "unconnected-(U1-PD6_(T1)-Pad49)") (class "Default")
      (node (ref "U1") (pin "49") (pinfunction "PD6_(T1)_49") (pintype "bidirectional+no_connect"))
    )
    (net (code "116") (name "unconnected-(U1-PE2_(XCK0{slash}AIN0)-Pad4)") (class "Default")
      (node (ref "U1") (pin "4") (pinfunction "PE2_(XCK0/AIN0)_4") (pintype "bidirectional"))
    )
    (net (code "117") (name "unconnected-(U1-PE6_(T3{slash}INT6)-Pad8)") (class "Default")
      (node (ref "U1") (pin "8") (pinfunction "PE6_(T3/INT6)_8") (pintype "bidirectional+no_connect"))
    )
    (net (code "118") (name "unconnected-(U1-PE7_(CLKO{slash}ICP3{slash}INT7)-Pad9)") (class "Default")
      (node (ref "U1") (pin "9") (pinfunction "PE7_(CLKO/ICP3/INT7)_9") (pintype "bidirectional+no_connect"))
    )
    (net (code "119") (name "unconnected-(U1-PG3_(TOSC2)-Pad28)") (class "Default")
      (node (ref "U1") (pin "28") (pinfunction "PG3_(TOSC2)_28") (pintype "bidirectional+no_connect"))
    )
    (net (code "120") (name "unconnected-(U1-PG4_(TOSC1)-Pad29)") (class "Default")
      (node (ref "U1") (pin "29") (pinfunction "PG4_(TOSC1)_29") (pintype "bidirectional+no_connect"))
    )
    (net (code "121") (name "unconnected-(U1-PH2_(XCK2)-Pad14)") (class "Default")
      (node (ref "U1") (pin "14") (pinfunction "PH2_(XCK2)_14") (pintype "bidirectional+no_connect"))
    )
    (net (code "122") (name "unconnected-(U1-PH7_(T4)-Pad27)") (class "Default")
      (node (ref "U1") (pin "27") (pinfunction "PH7_(T4)_27") (pintype "bidirectional+no_connect"))
    )
    (net (code "123") (name "unconnected-(U1-PJ2_(XCK3{slash}PCINT11)-Pad65)") (class "Default")
      (node (ref "U1") (pin "65") (pinfunction "PJ2_(XCK3/PCINT11)_65") (pintype "bidirectional+no_connect"))
    )
    (net (code "124") (name "unconnected-(U1-PJ3_(PCINT12)-Pad66)") (class "Default")
      (node (ref "U1") (pin "66") (pinfunction "PJ3_(PCINT12)_66") (pintype "bidirectional+no_connect"))
    )
    (net (code "125") (name "unconnected-(U1-PJ4_(PCINT13)-Pad67)") (class "Default")
      (node (ref "U1") (pin "67") (pinfunction "PJ4_(PCINT13)_67") (pintype "bidirectional+no_connect"))
    )
    (net (code "126") (name "unconnected-(U1-PJ5_(PCINT14)-Pad68)") (class "Default")
      (node (ref "U1") (pin "68") (pinfunction "PJ5_(PCINT14)_68") (pintype "bidirectional+no_connect"))
    )
    (net (code "127") (name "unconnected-(U1-PJ6_(PCINT15)-Pad69)") (class "Default")
      (node (ref "U1") (pin "69") (pinfunction "PJ6_(PCINT15)_69") (pintype "bidirectional+no_connect"))
    )
    (net (code "128") (name "unconnected-(U1-PJ7-Pad79)") (class "Default")
      (node (ref "U1") (pin "79") (pinfunction "PJ7_79") (pintype "bidirectional+no_connect"))
    )
    (net (code "129") (name "unconnected-(U2-AIN0_{slash}_INT1_{slash}_PD1-Pad7)") (class "Default")
      (node (ref "U2") (pin "7") (pinfunction "AIN0_/_INT1_/_PD1_7") (pintype "passive+no_connect"))
    )
    (net (code "130") (name "unconnected-(U2-AIN2_{slash}_PCINT11_{slash}_PC2-Pad5)") (class "Default")
      (node (ref "U2") (pin "5") (pinfunction "AIN2_/_PCINT11_/_PC2_5") (pintype "passive+no_connect"))
    )
    (net (code "131") (name "unconnected-(U2-CLKO_{slash}_ICP1_{slash}_INT4_{slash}_PC7-Pad22)") (class "Default")
      (node (ref "U2") (pin "22") (pinfunction "CLKO_/_ICP1_/_INT4_/_PC7_22") (pintype "passive+no_connect"))
    )
    (net (code "132") (name "unconnected-(U2-OC.0B_{slash}_INT0_{slash}_PD0-Pad6)") (class "Default")
      (node (ref "U2") (pin "6") (pinfunction "OC.0B_/_INT0_/_PD0_6") (pintype "passive+no_connect"))
    )
    (net (code "133") (name "unconnected-(U2-OC.1A_{slash}_PCINT8_{slash}_PC6-Pad23)") (class "Default")
      (node (ref "U2") (pin "23") (pinfunction "OC.1A_/_PCINT8_/_PC6_23") (pintype "passive+no_connect"))
    )
    (net (code "134") (name "unconnected-(U2-OC.1B_{slash}_PCINT9_{slash}_PC5-Pad25)") (class "Default")
      (node (ref "U2") (pin "25") (pinfunction "OC.1B_/_PCINT9_/_PC5_25") (pintype "passive+no_connect"))
    )
    (net (code "135") (name "unconnected-(U2-PCINT10_{slash}_PC4-Pad26)") (class "Default")
      (node (ref "U2") (pin "26") (pinfunction "PCINT10_/_PC4_26") (pintype "passive+no_connect"))
    )
    (net (code "136") (name "unconnected-(U2-~{RTS}_{slash}_AIN5_{slash}_INT6_{slash}_PD6-Pad12)") (class "Default")
      (node (ref "U2") (pin "12") (pinfunction "~{RTS}_/_AIN5_/_INT6_/_PD6_12") (pintype "passive+no_connect"))
    )
    (net (code "137") (name "unconnected-(U2-~{SS}_{slash}_PCINT0_{slash}_PB0-Pad14)") (class "Default")
      (node (ref "U2") (pin "14") (pinfunction "~{SS}_/_PCINT0_/_PB0_14") (pintype "passive+no_connect"))
    )
  )
)
